# PWM_OUTPUT.net
KiCad netlist of a schematic drawn in Altium Designer
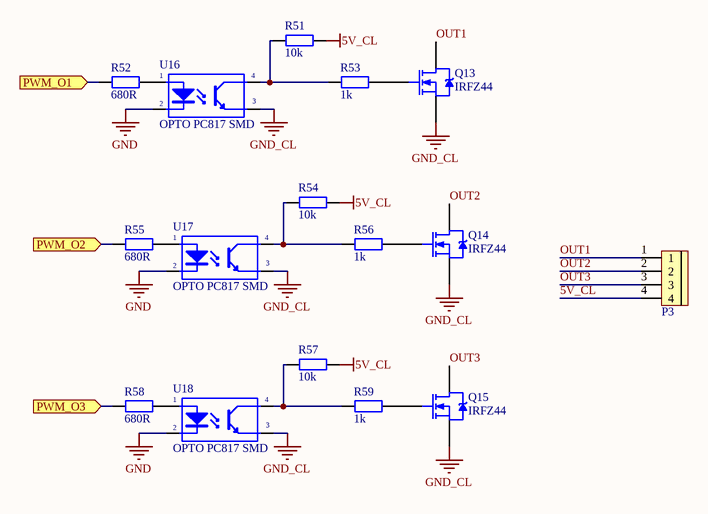
[diagram p0: PWM_OUTPUT.SchDoc]

(export (version "E")
  (design (tool "Eeschema 10.0.6"))
  (components
    (comp (ref "P3")
      (value "CON 4 EDG5.08")
      (footprint "CON 4 4EDG5.08")
      (description "Cắm")
      (libsource (lib "Altium_Lib_by_KhueNguyenCreator") (part "CON 4 EDG5.08"))
    )
    (comp (ref "Q13")
      (value "IRFZ44")
      (footprint "TO220")
      (description "N-Channel Power MOSFET")
      (libsource (lib "Altium_Lib_by_KhueNguyenCreator") (part "IRFZ44 DIP"))
    )
    (comp (ref "Q14")
      (value "IRFZ44")
      (footprint "TO220")
      (description "N-Channel Power MOSFET")
      (libsource (lib "Altium_Lib_by_KhueNguyenCreator") (part "IRFZ44 DIP"))
    )
    (comp (ref "Q15")
      (value "IRFZ44")
      (footprint "TO220")
      (description "N-Channel Power MOSFET")
      (libsource (lib "Altium_Lib_by_KhueNguyenCreator") (part "IRFZ44 DIP"))
    )
    (comp (ref "R51")
      (value "10k")
      (footprint "tro smd 0805")
      (description "Dán")
      (libsource (lib "Altium_Lib_by_KhueNguyenCreator") (part "Tro 0805 1% 10k"))
    )
    (comp (ref "R52")
      (value "680R")
      (footprint "tro smd 0805")
      (description "Dán")
      (libsource (lib "Altium_Lib_by_KhueNguyenCreator") (part "Tro 0805 1% 680R"))
    )
    (comp (ref "R53")
      (value "1k")
      (footprint "tro smd 0805")
      (description "Dán")
      (libsource (lib "Altium_Lib_by_KhueNguyenCreator") (part "Tro 0805 1% 1k"))
    )
    (comp (ref "R54")
      (value "10k")
      (footprint "tro smd 0805")
      (description "Dán")
      (libsource (lib "Altium_Lib_by_KhueNguyenCreator") (part "Tro 0805 1% 10k"))
    )
    (comp (ref "R55")
      (value "680R")
      (footprint "tro smd 0805")
      (description "Dán")
      (libsource (lib "Altium_Lib_by_KhueNguyenCreator") (part "Tro 0805 1% 680R"))
    )
    (comp (ref "R56")
      (value "1k")
      (footprint "tro smd 0805")
      (description "Dán")
      (libsource (lib "Altium_Lib_by_KhueNguyenCreator") (part "Tro 0805 1% 1k"))
    )
    (comp (ref "R57")
      (value "10k")
      (footprint "tro smd 0805")
      (description "Dán")
      (libsource (lib "Altium_Lib_by_KhueNguyenCreator") (part "Tro 0805 1% 10k"))
    )
    (comp (ref "R58")
      (value "680R")
      (footprint "tro smd 0805")
      (description "Dán")
      (libsource (lib "Altium_Lib_by_KhueNguyenCreator") (part "Tro 0805 1% 680R"))
    )
    (comp (ref "R59")
      (value "1k")
      (footprint "tro smd 0805")
      (description "Dán")
      (libsource (lib "Altium_Lib_by_KhueNguyenCreator") (part "Tro 0805 1% 1k"))
    )
    (comp (ref "U16")
      (value "OPTO PC817 SMD")
      (footprint "SOP4")
      (description "Single Opto")
      (libsource (lib "Altium_Lib_by_KhueNguyenCreator") (part "OPTO PC817 SMD"))
    )
    (comp (ref "U17")
      (value "OPTO PC817 SMD")
      (footprint "SOP4")
      (description "Single Opto")
      (libsource (lib "Altium_Lib_by_KhueNguyenCreator") (part "OPTO PC817 SMD"))
    )
    (comp (ref "U18")
      (value "OPTO PC817 SMD")
      (footprint "SOP4")
      (description "Single Opto")
      (libsource (lib "Altium_Lib_by_KhueNguyenCreator") (part "OPTO PC817 SMD"))
    )
  )
  (nets
    (net (code "1") (name "/OUT1") (class "Default")
      (node (ref "P3") (pin "1") (pinfunction "1_1") (pintype "passive"))
      (node (ref "Q13") (pin "2") (pinfunction "D_2") (pintype "passive"))
    )
    (net (code "2") (name "/OUT2") (class "Default")
      (node (ref "P3") (pin "2") (pinfunction "2_2") (pintype "passive"))
      (node (ref "Q14") (pin "2") (pinfunction "D_2") (pintype "passive"))
    )
    (net (code "3") (name "/OUT3") (class "Default")
      (node (ref "P3") (pin "3") (pinfunction "3_3") (pintype "passive"))
      (node (ref "Q15") (pin "2") (pinfunction "D_2") (pintype "passive"))
    )
    (net (code "4") (name "/PWM_O1") (class "Default")
      (node (ref "R52") (pin "1") (pinfunction "1_1") (pintype "passive"))
    )
    (net (code "5") (name "/PWM_O2") (class "Default")
      (node (ref "R55") (pin "1") (pinfunction "1_1") (pintype "passive"))
    )
    (net (code "6") (name "/PWM_O3") (class "Default")
      (node (ref "R58") (pin "1") (pinfunction "1_1") (pintype "passive"))
    )
    (net (code "7") (name "5V_CL") (class "Default")
      (node (ref "P3") (pin "4") (pinfunction "4_4") (pintype "passive"))
      (node (ref "R51") (pin "1") (pinfunction "1_1") (pintype "passive"))
      (node (ref "R54") (pin "1") (pinfunction "1_1") (pintype "passive"))
      (node (ref "R57") (pin "1") (pinfunction "1_1") (pintype "passive"))
    )
    (net (code "8") (name "GND") (class "Default")
      (node (ref "U16") (pin "2") (pinfunction "K_2") (pintype "passive"))
      (node (ref "U17") (pin "2") (pinfunction "K_2") (pintype "passive"))
      (node (ref "U18") (pin "2") (pinfunction "K_2") (pintype "passive"))
    )
    (net (code "9") (name "GND_CL") (class "Default")
      (node (ref "Q13") (pin "3") (pinfunction "S_3") (pintype "passive"))
      (node (ref "Q14") (pin "3") (pinfunction "S_3") (pintype "passive"))
      (node (ref "Q15") (pin "3") (pinfunction "S_3") (pintype "passive"))
      (node (ref "U16") (pin "3") (pinfunction "E_3") (pintype "passive"))
      (node (ref "U17") (pin "3") (pinfunction "E_3") (pintype "passive"))
      (node (ref "U18") (pin "3") (pinfunction "E_3") (pintype "passive"))
    )
    (net (code "10") (name "Net-(Q13-G)") (class "Default")
      (node (ref "Q13") (pin "1") (pinfunction "G_1") (pintype "passive"))
      (node (ref "R53") (pin "2") (pinfunction "2_2") (pintype "passive"))
    )
    (net (code "11") (name "Net-(Q14-G)") (class "Default")
      (node (ref "Q14") (pin "1") (pinfunction "G_1") (pintype "passive"))
      (node (ref "R56") (pin "2") (pinfunction "2_2") (pintype "passive"))
    )
    (net (code "12") (name "Net-(Q15-G)") (class "Default")
      (node (ref "Q15") (pin "1") (pinfunction "G_1") (pintype "passive"))
      (node (ref "R59") (pin "2") (pinfunction "2_2") (pintype "passive"))
    )
    (net (code "13") (name "Net-(U16-A)") (class "Default")
      (node (ref "R52") (pin "2") (pinfunction "2_2") (pintype "passive"))
      (node (ref "U16") (pin "1") (pinfunction "A_1") (pintype "passive"))
    )
    (net (code "14") (name "Net-(U16-C)") (class "Default")
      (node (ref "R51") (pin "2") (pinfunction "2_2") (pintype "passive"))
      (node (ref "R53") (pin "1") (pinfunction "1_1") (pintype "passive"))
      (node (ref "U16") (pin "4") (pinfunction "C_4") (pintype "passive"))
    )
    (net (code "15") (name "Net-(U17-A)") (class "Default")
      (node (ref "R55") (pin "2") (pinfunction "2_2") (pintype "passive"))
      (node (ref "U17") (pin "1") (pinfunction "A_1") (pintype "passive"))
    )
    (net (code "16") (name "Net-(U17-C)") (class "Default")
      (node (ref "R54") (pin "2") (pinfunction "2_2") (pintype "passive"))
      (node (ref "R56") (pin "1") (pinfunction "1_1") (pintype "passive"))
      (node (ref "U17") (pin "4") (pinfunction "C_4") (pintype "passive"))
    )
    (net (code "17") (name "Net-(U18-A)") (class "Default")
      (node (ref "R58") (pin "2") (pinfunction "2_2") (pintype "passive"))
      (node (ref "U18") (pin "1") (pinfunction "A_1") (pintype "passive"))
    )
    (net (code "18") (name "Net-(U18-C)") (class "Default")
      (node (ref "R57") (pin "2") (pinfunction "2_2") (pintype "passive"))
      (node (ref "R59") (pin "1") (pinfunction "1_1") (pintype "passive"))
      (node (ref "U18") (pin "4") (pinfunction "C_4") (pintype "passive"))
    )
  )
)
